# Airq_altium.net
KiCad netlist of a schematic drawn in Altium Designer
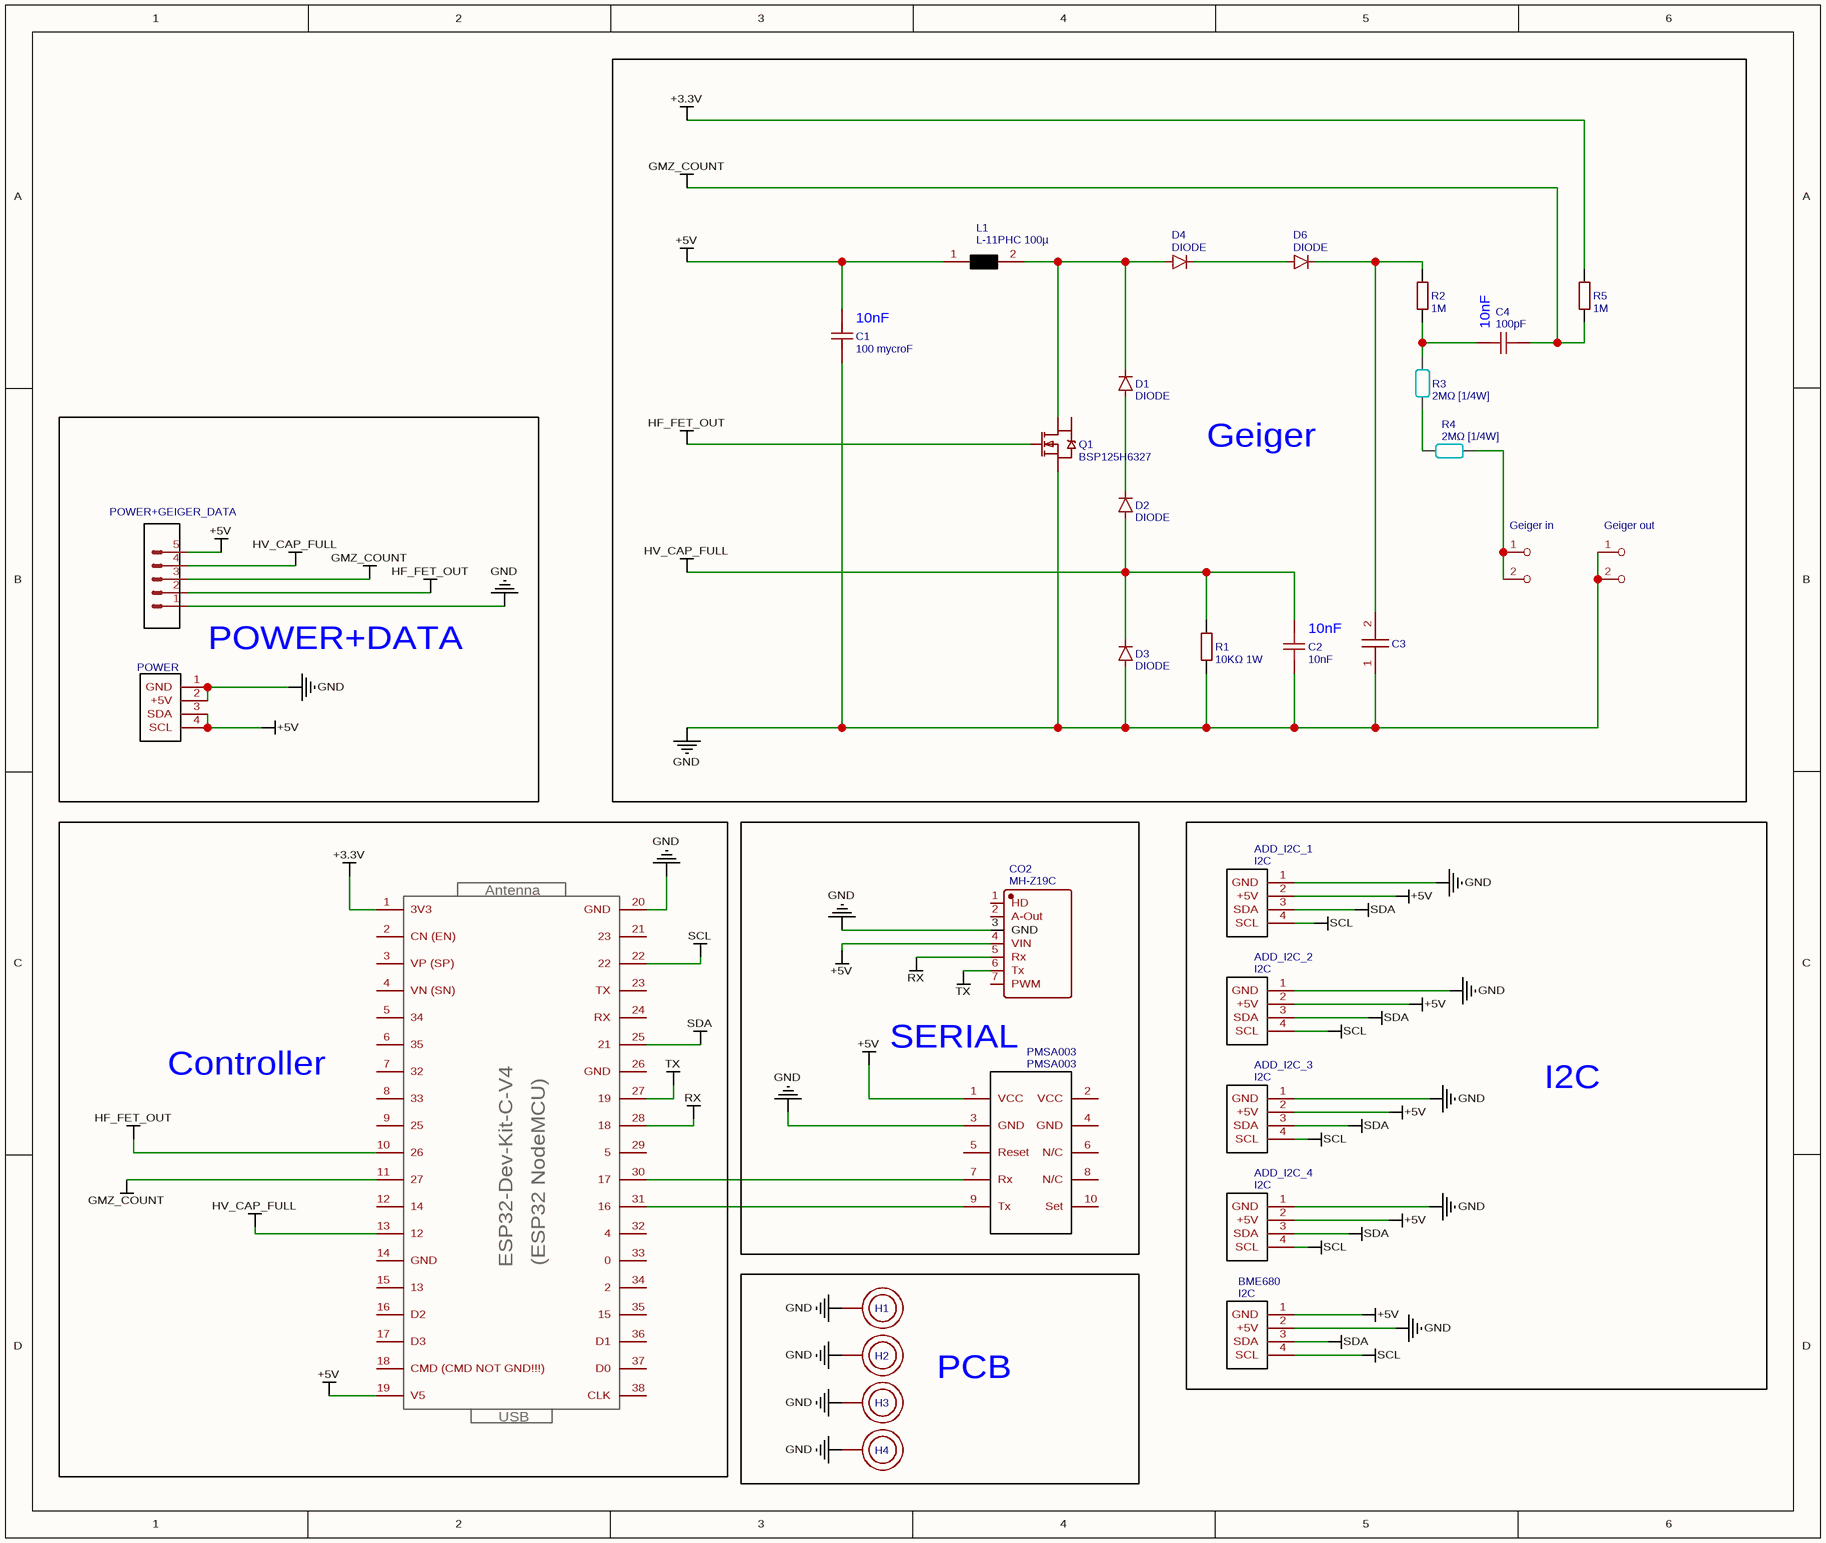
[diagram p0: Airq_altium.schdoc]

(export (version "E")
  (design (tool "Eeschema 10.0.6"))
  (components
    (comp (ref "ADD_I2C_1")
      (value "I2C")
      (fields (field (name "CONTRIBUTOR") "paultwick"))
      (libsource (lib "altium-import") (part "root_0_I2C_"))
    )
    (comp (ref "ADD_I2C_2")
      (value "I2C")
      (fields (field (name "CONTRIBUTOR") "paultwick"))
      (libsource (lib "altium-import") (part "root_0_I2C_"))
    )
    (comp (ref "ADD_I2C_3")
      (value "I2C")
      (fields (field (name "CONTRIBUTOR") "paultwick"))
      (libsource (lib "altium-import") (part "root_0_I2C_"))
    )
    (comp (ref "ADD_I2C_4")
      (value "I2C")
      (fields (field (name "CONTRIBUTOR") "paultwick"))
      (libsource (lib "altium-import") (part "root_0_I2C_"))
    )
    (comp (ref "BME680")
      (value "I2C")
      (fields (field (name "CONTRIBUTOR") "paultwick"))
      (libsource (lib "altium-import") (part "root_0_I2C_"))
    )
    (comp (ref "C1")
      (value "100 mycroF")
      (fields (field (name "CONTRIBUTOR") "Shant Centistoke"))
      (libsource (lib "altium-import") (part "root_0_100 mycroF_"))
    )
    (comp (ref "C2")
      (value "10nF")
      (fields (field (name "CONTRIBUTOR") "Shant Centistoke"))
      (libsource (lib "altium-import") (part "root_0_10nF_"))
    )
    (comp (ref "C3")
      (value "Wima, MKP4, 100nF, 630V")
      (fields (field (name "CONTRIBUTOR") "Hotte"))
      (libsource (lib "altium-import") (part "root_1_Wima, MKP4, 100nF, 630V_"))
    )
    (comp (ref "C4")
      (value "100pF")
      (fields (field (name "CONTRIBUTOR") "Shant Centistoke"))
      (libsource (lib "altium-import") (part "root_1_100pF_"))
    )
    (comp (ref "CO2")
      (value "MH-Z19C")
      (fields
        (field (name "BOM_SUPPLIER PART") "https://github.com/WifWaf/MH-Z19/tree/master/examples/BasicUsage")
        (field (name "CONTRIBUTOR") "Ralf-Michael von Prondzinski")
      )
      (libsource (lib "altium-import") (part "root_0_MH-Z19C_"))
    )
    (comp (ref "D1")
      (value "DIODE")
      (description "Diode")
      (libsource (lib "altium-import") (part "root_1_DIODE_"))
    )
    (comp (ref "D2")
      (value "DIODE")
      (description "Diode")
      (libsource (lib "altium-import") (part "root_1_DIODE_"))
    )
    (comp (ref "D3")
      (value "DIODE")
      (description "Diode")
      (libsource (lib "altium-import") (part "root_1_DIODE_"))
    )
    (comp (ref "D4")
      (value "DIODE")
      (description "Diode")
      (libsource (lib "altium-import") (part "root_0_DIODE_"))
    )
    (comp (ref "D6")
      (value "DIODE")
      (description "Diode")
      (libsource (lib "altium-import") (part "root_0_DIODE_"))
    )
    (comp (ref "H1")
      (value "HoleHole")
      (fields (field (name "CONTRIBUTOR") "Cillié Malan"))
      (libsource (lib "altium-import") (part "root_0_HoleHole_"))
    )
    (comp (ref "H2")
      (value "HoleHole")
      (fields (field (name "CONTRIBUTOR") "Cillié Malan"))
      (libsource (lib "altium-import") (part "root_0_HoleHole_"))
    )
    (comp (ref "H3")
      (value "HoleHole")
      (fields (field (name "CONTRIBUTOR") "Cillié Malan"))
      (libsource (lib "altium-import") (part "root_0_HoleHole_"))
    )
    (comp (ref "H4")
      (value "HoleHole")
      (fields (field (name "CONTRIBUTOR") "Cillié Malan"))
      (libsource (lib "altium-import") (part "root_0_HoleHole_"))
    )
    (comp (ref "JP1")
      (value "Geiger in")
      (fields (field (name "CONTRIBUTOR") "Adafruit"))
      (libsource (lib "altium-import") (part "root_0_Geiger in_"))
    )
    (comp (ref "JP2")
      (value "Geiger out")
      (fields (field (name "CONTRIBUTOR") "Adafruit"))
      (libsource (lib "altium-import") (part "root_0_Geiger out_"))
    )
    (comp (ref "L1")
      (value "L-11PHC 100µ")
      (fields (field (name "CONTRIBUTOR") "Bagger"))
      (libsource (lib "altium-import") (part "root_0_L-11PHC 100µ_"))
    )
    (comp (ref "PMSA003")
      (value "PMSA003")
      (fields (field (name "CONTRIBUTOR") "rajsiman"))
      (libsource (lib "altium-import") (part "root_0_PMSA003_"))
    )
    (comp (ref "POWER")
      (value "Power")
      (fields (field (name "CONTRIBUTOR") "paultwick"))
      (libsource (lib "altium-import") (part "root_0_Power_"))
    )
    (comp (ref "POWER+GEIGER_DATA")
      (value "POWER+GEIGER_DATA")
      (description "5 x 0.1 inch Header")
      (fields (field (name "CONTRIBUTOR") "SparkFun"))
      (libsource (lib "altium-import") (part "root_0_POWER+GEIGER_DATA_"))
    )
    (comp (ref "Q1")
      (value "BSP125H6327")
      (fields (field (name "BOM_SUPPLIER PART") "C123756") (field (name "CONTRIBUTOR") "LCSC"))
      (libsource (lib "altium-import") (part "root_0_BSP125H6327_"))
    )
    (comp (ref "R1")
      (value "10KΩ 1W")
      (fields
        (field (name "BOM_MANUFACTURER PART") "MFR0W4F1004A50")
        (field (name "BOM_SUPPLIER PART") "C58596")
      )
      (libsource (lib "altium-import") (part "root_1_10KΩ 1W_"))
    )
    (comp (ref "R2")
      (value "1M")
      (fields
        (field (name "BOM_MANUFACTURER PART") "MFR0W4F1004A50")
        (field (name "BOM_SUPPLIER PART") "C58596")
      )
      (libsource (lib "altium-import") (part "root_1_1M_"))
    )
    (comp (ref "R3")
      (value "2MΩ [1/4W]")
      (fields
        (field (name "BOM_SUPPLIER PART") "C720290")
        (field (name "CONTRIBUTOR") "Harwave Technologies")
      )
      (libsource (lib "altium-import") (part "root_1_2MΩ [1/4W]_"))
    )
    (comp (ref "R4")
      (value "2MΩ [1/4W]")
      (fields
        (field (name "BOM_SUPPLIER PART") "C720290")
        (field (name "CONTRIBUTOR") "Harwave Technologies")
      )
      (libsource (lib "altium-import") (part "root_0_2MΩ [1/4W]_"))
    )
    (comp (ref "R5")
      (value "1M")
      (fields
        (field (name "BOM_MANUFACTURER PART") "MFR0W4F1004A50")
        (field (name "BOM_SUPPLIER PART") "C58596")
      )
      (libsource (lib "altium-import") (part "root_3_1M_"))
    )
    (comp (ref "U1")
      (value "AZDelivery_ESP32_NodeMCU")
      (fields (field (name "CONTRIBUTOR") "Andreas Riepl"))
      (libsource (lib "altium-import") (part "root_0_AZDelivery_ESP32_NodeMCU_"))
    )
  )
  (nets
    (net (code "1") (name "+3.3V") (class "Default")
      (node (ref "R5") (pin "1") (pinfunction "1_1") (pintype "passive"))
      (node (ref "U1") (pin "1") (pinfunction "3V3_1") (pintype "passive"))
    )
    (net (code "2") (name "+5V") (class "Default")
      (node (ref "ADD_I2C_1") (pin "2") (pinfunction "+5V_2") (pintype "passive"))
      (node (ref "ADD_I2C_2") (pin "2") (pinfunction "+5V_2") (pintype "passive"))
      (node (ref "ADD_I2C_3") (pin "2") (pinfunction "+5V_2") (pintype "passive"))
      (node (ref "ADD_I2C_4") (pin "2") (pinfunction "+5V_2") (pintype "passive"))
      (node (ref "BME680") (pin "1") (pinfunction "GND_1") (pintype "passive"))
      (node (ref "C1") (pin "2") (pinfunction "2_2") (pintype "passive"))
      (node (ref "CO2") (pin "4") (pinfunction "VIN_4") (pintype "passive"))
      (node (ref "L1") (pin "1") (pinfunction "1_1") (pintype "passive"))
      (node (ref "PMSA003") (pin "1") (pinfunction "VCC_1") (pintype "passive"))
      (node (ref "POWER") (pin "3") (pinfunction "SDA_3") (pintype "passive"))
      (node (ref "POWER") (pin "4") (pinfunction "SCL_4") (pintype "passive"))
      (node (ref "POWER+GEIGER_DATA") (pin "5") (pinfunction "1_5") (pintype "passive"))
      (node (ref "U1") (pin "19") (pinfunction "V5_19") (pintype "passive"))
    )
    (net (code "3") (name "GMZ_COUNT") (class "Default")
      (node (ref "C4") (pin "1") (pinfunction "1_1") (pintype "passive"))
      (node (ref "POWER+GEIGER_DATA") (pin "3") (pinfunction "1_3") (pintype "passive"))
      (node (ref "R5") (pin "2") (pinfunction "2_2") (pintype "passive"))
      (node (ref "U1") (pin "11") (pinfunction "27_11") (pintype "passive"))
    )
    (net (code "4") (name "GND") (class "Default")
      (node (ref "ADD_I2C_1") (pin "1") (pinfunction "GND_1") (pintype "passive"))
      (node (ref "ADD_I2C_2") (pin "1") (pinfunction "GND_1") (pintype "passive"))
      (node (ref "ADD_I2C_3") (pin "1") (pinfunction "GND_1") (pintype "passive"))
      (node (ref "ADD_I2C_4") (pin "1") (pinfunction "GND_1") (pintype "passive"))
      (node (ref "BME680") (pin "2") (pinfunction "+5V_2") (pintype "passive"))
      (node (ref "C1") (pin "1") (pinfunction "1_1") (pintype "passive"))
      (node (ref "C2") (pin "1") (pinfunction "1_1") (pintype "passive"))
      (node (ref "C3") (pin "1") (pinfunction "1_1") (pintype "passive"))
      (node (ref "CO2") (pin "3") (pinfunction "GND_3") (pintype "passive"))
      (node (ref "D3") (pin "A") (pinfunction "A_A") (pintype "passive"))
      (node (ref "H1") (pin "1") (pinfunction "1_1") (pintype "passive"))
      (node (ref "H2") (pin "1") (pinfunction "1_1") (pintype "passive"))
      (node (ref "H3") (pin "1") (pinfunction "1_1") (pintype "passive"))
      (node (ref "H4") (pin "1") (pinfunction "1_1") (pintype "passive"))
      (node (ref "JP2") (pin "1") (pinfunction "1_1") (pintype "passive"))
      (node (ref "JP2") (pin "2") (pinfunction "2_2") (pintype "passive"))
      (node (ref "PMSA003") (pin "3") (pinfunction "GND_3") (pintype "passive"))
      (node (ref "POWER") (pin "1") (pinfunction "GND_1") (pintype "passive"))
      (node (ref "POWER") (pin "2") (pinfunction "+5V_2") (pintype "passive"))
      (node (ref "POWER+GEIGER_DATA") (pin "1") (pinfunction "1_1") (pintype "passive"))
      (node (ref "Q1") (pin "3") (pinfunction "S_3") (pintype "passive"))
      (node (ref "R1") (pin "1") (pinfunction "1_1") (pintype "passive"))
      (node (ref "U1") (pin "20") (pinfunction "GND_20") (pintype "passive"))
    )
    (net (code "5") (name "HF_FET_OUT") (class "Default")
      (node (ref "POWER+GEIGER_DATA") (pin "2") (pinfunction "2_2") (pintype "passive"))
      (node (ref "Q1") (pin "1") (pinfunction "G_1") (pintype "passive"))
      (node (ref "U1") (pin "10") (pinfunction "26_10") (pintype "passive"))
    )
    (net (code "6") (name "HV_CAP_FULL") (class "Default")
      (node (ref "C2") (pin "2") (pinfunction "2_2") (pintype "passive"))
      (node (ref "D2") (pin "A") (pinfunction "A_A") (pintype "passive"))
      (node (ref "D3") (pin "C") (pinfunction "C_C") (pintype "passive"))
      (node (ref "POWER+GEIGER_DATA") (pin "4") (pinfunction "2_4") (pintype "passive"))
      (node (ref "R1") (pin "2") (pinfunction "2_2") (pintype "passive"))
      (node (ref "U1") (pin "13") (pinfunction "12_13") (pintype "passive"))
    )
    (net (code "7") (name "Net-(C3-Pad2)") (class "Default")
      (node (ref "C3") (pin "2") (pinfunction "2_2") (pintype "passive"))
      (node (ref "D6") (pin "C") (pinfunction "C_C") (pintype "passive"))
      (node (ref "R2") (pin "2") (pinfunction "2_2") (pintype "passive"))
    )
    (net (code "8") (name "Net-(C4-Pad2)") (class "Default")
      (node (ref "C4") (pin "2") (pinfunction "2_2") (pintype "passive"))
      (node (ref "R2") (pin "1") (pinfunction "1_1") (pintype "passive"))
      (node (ref "R3") (pin "2") (pinfunction "2_2") (pintype "passive"))
    )
    (net (code "9") (name "Net-(D1-PadA)") (class "Default")
      (node (ref "D1") (pin "A") (pinfunction "A_A") (pintype "passive"))
      (node (ref "D2") (pin "C") (pinfunction "C_C") (pintype "passive"))
    )
    (net (code "10") (name "Net-(D1-PadC)") (class "Default")
      (node (ref "D1") (pin "C") (pinfunction "C_C") (pintype "passive"))
      (node (ref "D4") (pin "A") (pinfunction "A_A") (pintype "passive"))
      (node (ref "L1") (pin "2") (pinfunction "2_2") (pintype "passive"))
      (node (ref "Q1") (pin "2") (pinfunction "D_2") (pintype "passive"))
    )
    (net (code "11") (name "Net-(D4-PadC)") (class "Default")
      (node (ref "D4") (pin "C") (pinfunction "C_C") (pintype "passive"))
      (node (ref "D6") (pin "A") (pinfunction "A_A") (pintype "passive"))
    )
    (net (code "12") (name "Net-(JP1-Pad1)") (class "Default")
      (node (ref "JP1") (pin "1") (pinfunction "1_1") (pintype "passive"))
      (node (ref "JP1") (pin "2") (pinfunction "2_2") (pintype "passive"))
      (node (ref "R4") (pin "2") (pinfunction "2_2") (pintype "passive"))
    )
    (net (code "13") (name "Net-(PMSA003-Rx)") (class "Default")
      (node (ref "PMSA003") (pin "7") (pinfunction "Rx_7") (pintype "passive"))
      (node (ref "U1") (pin "30") (pinfunction "17_30") (pintype "passive"))
    )
    (net (code "14") (name "Net-(PMSA003-Tx)") (class "Default")
      (node (ref "PMSA003") (pin "9") (pinfunction "Tx_9") (pintype "passive"))
      (node (ref "U1") (pin "31") (pinfunction "16_31") (pintype "passive"))
    )
    (net (code "15") (name "Net-(R3-Pad1)") (class "Default")
      (node (ref "R3") (pin "1") (pinfunction "1_1") (pintype "passive"))
      (node (ref "R4") (pin "1") (pinfunction "1_1") (pintype "passive"))
    )
    (net (code "16") (name "RX") (class "Default")
      (node (ref "CO2") (pin "5") (pinfunction "Rx_5") (pintype "passive"))
      (node (ref "U1") (pin "28") (pinfunction "18_28") (pintype "passive"))
    )
    (net (code "17") (name "SCL") (class "Default")
      (node (ref "ADD_I2C_1") (pin "4") (pinfunction "SCL_4") (pintype "passive"))
      (node (ref "ADD_I2C_2") (pin "4") (pinfunction "SCL_4") (pintype "passive"))
      (node (ref "ADD_I2C_3") (pin "4") (pinfunction "SCL_4") (pintype "passive"))
      (node (ref "ADD_I2C_4") (pin "4") (pinfunction "SCL_4") (pintype "passive"))
      (node (ref "BME680") (pin "4") (pinfunction "SCL_4") (pintype "passive"))
      (node (ref "U1") (pin "22") (pinfunction "22_22") (pintype "passive"))
    )
    (net (code "18") (name "SDA") (class "Default")
      (node (ref "ADD_I2C_1") (pin "3") (pinfunction "SDA_3") (pintype "passive"))
      (node (ref "ADD_I2C_2") (pin "3") (pinfunction "SDA_3") (pintype "passive"))
      (node (ref "ADD_I2C_3") (pin "3") (pinfunction "SDA_3") (pintype "passive"))
      (node (ref "ADD_I2C_4") (pin "3") (pinfunction "SDA_3") (pintype "passive"))
      (node (ref "BME680") (pin "3") (pinfunction "SDA_3") (pintype "passive"))
      (node (ref "U1") (pin "25") (pinfunction "21_25") (pintype "passive"))
    )
    (net (code "19") (name "TX") (class "Default")
      (node (ref "CO2") (pin "6") (pinfunction "Tx_6") (pintype "passive"))
      (node (ref "U1") (pin "27") (pinfunction "19_27") (pintype "passive"))
    )
    (net (code "20") (name "unconnected-(CO2-A-Out-Pad2)") (class "Default")
      (node (ref "CO2") (pin "2") (pinfunction "A-Out_2") (pintype "passive"))
    )
    (net (code "21") (name "unconnected-(CO2-HD-Pad1)") (class "Default")
      (node (ref "CO2") (pin "1") (pinfunction "HD_1") (pintype "passive"))
    )
    (net (code "22") (name "unconnected-(CO2-PWM-Pad7)") (class "Default")
      (node (ref "CO2") (pin "7") (pinfunction "PWM_7") (pintype "passive"))
    )
    (net (code "23") (name "unconnected-(PMSA003-GND-Pad4)") (class "Default")
      (node (ref "PMSA003") (pin "4") (pinfunction "GND_4") (pintype "passive"))
    )
    (net (code "24") (name "unconnected-(PMSA003-N{slash}C-Pad6)") (class "Default")
      (node (ref "PMSA003") (pin "6") (pinfunction "N/C_6") (pintype "passive"))
    )
    (net (code "25") (name "unconnected-(PMSA003-N{slash}C-Pad8)") (class "Default")
      (node (ref "PMSA003") (pin "8") (pinfunction "N/C_8") (pintype "passive"))
    )
    (net (code "26") (name "unconnected-(PMSA003-Reset-Pad5)") (class "Default")
      (node (ref "PMSA003") (pin "5") (pinfunction "Reset_5") (pintype "passive"))
    )
    (net (code "27") (name "unconnected-(PMSA003-Set-Pad10)") (class "Default")
      (node (ref "PMSA003") (pin "10") (pinfunction "Set_10") (pintype "passive"))
    )
    (net (code "28") (name "unconnected-(PMSA003-VCC-Pad2)") (class "Default")
      (node (ref "PMSA003") (pin "2") (pinfunction "VCC_2") (pintype "passive"))
    )
    (net (code "29") (name "unconnected-(Q1-D-Pad4)") (class "Default")
      (node (ref "Q1") (pin "4") (pinfunction "D_4") (pintype "passive"))
    )
    (net (code "30") (name "unconnected-(U1-0-Pad33)") (class "Default")
      (node (ref "U1") (pin "33") (pinfunction "0_33") (pintype "passive"))
    )
    (net (code "31") (name "unconnected-(U1-2-Pad34)") (class "Default")
      (node (ref "U1") (pin "34") (pinfunction "2_34") (pintype "passive"))
    )
    (net (code "32") (name "unconnected-(U1-4-Pad32)") (class "Default")
      (node (ref "U1") (pin "32") (pinfunction "4_32") (pintype "passive"))
    )
    (net (code "33") (name "unconnected-(U1-5-Pad29)") (class "Default")
      (node (ref "U1") (pin "29") (pinfunction "5_29") (pintype "passive"))
    )
    (net (code "34") (name "unconnected-(U1-13-Pad15)") (class "Default")
      (node (ref "U1") (pin "15") (pinfunction "13_15") (pintype "passive"))
    )
    (net (code "35") (name "unconnected-(U1-14-Pad12)") (class "Default")
      (node (ref "U1") (pin "12") (pinfunction "14_12") (pintype "passive"))
    )
    (net (code "36") (name "unconnected-(U1-15-Pad35)") (class "Default")
      (node (ref "U1") (pin "35") (pinfunction "15_35") (pintype "passive"))
    )
    (net (code "37") (name "unconnected-(U1-23-Pad21)") (class "Default")
      (node (ref "U1") (pin "21") (pinfunction "23_21") (pintype "passive"))
    )
    (net (code "38") (name "unconnected-(U1-25-Pad9)") (class "Default")
      (node (ref "U1") (pin "9") (pinfunction "25_9") (pintype "passive"))
    )
    (net (code "39") (name "unconnected-(U1-32-Pad7)") (class "Default")
      (node (ref "U1") (pin "7") (pinfunction "32_7") (pintype "passive"))
    )
    (net (code "40") (name "unconnected-(U1-33-Pad8)") (class "Default")
      (node (ref "U1") (pin "8") (pinfunction "33_8") (pintype "passive"))
    )
    (net (code "41") (name "unconnected-(U1-34-Pad5)") (class "Default")
      (node (ref "U1") (pin "5") (pinfunction "34_5") (pintype "passive"))
    )
    (net (code "42") (name "unconnected-(U1-35-Pad6)") (class "Default")
      (node (ref "U1") (pin "6") (pinfunction "35_6") (pintype "passive"))
    )
    (net (code "43") (name "unconnected-(U1-CLK-Pad38)") (class "Default")
      (node (ref "U1") (pin "38") (pinfunction "CLK_38") (pintype "passive"))
    )
    (net (code "44") (name "unconnected-(U1-CMD_(CMD_NOT_GND!!!)-Pad18)") (class "Default")
      (node (ref "U1") (pin "18") (pinfunction "CMD_(CMD_NOT_GND!!!)_18") (pintype "passive"))
    )
    (net (code "45") (name "unconnected-(U1-CN_(EN)-Pad2)") (class "Default")
      (node (ref "U1") (pin "2") (pinfunction "CN_(EN)_2") (pintype "passive"))
    )
    (net (code "46") (name "unconnected-(U1-D0-Pad37)") (class "Default")
      (node (ref "U1") (pin "37") (pinfunction "D0_37") (pintype "passive"))
    )
    (net (code "47") (name "unconnected-(U1-D1-Pad36)") (class "Default")
      (node (ref "U1") (pin "36") (pinfunction "D1_36") (pintype "passive"))
    )
    (net (code "48") (name "unconnected-(U1-D2-Pad16)") (class "Default")
      (node (ref "U1") (pin "16") (pinfunction "D2_16") (pintype "passive"))
    )
    (net (code "49") (name "unconnected-(U1-D3-Pad17)") (class "Default")
      (node (ref "U1") (pin "17") (pinfunction "D3_17") (pintype "passive"))
    )
    (net (code "50") (name "unconnected-(U1-GND-Pad14)") (class "Default")
      (node (ref "U1") (pin "14") (pinfunction "GND_14") (pintype "passive"))
    )
    (net (code "51") (name "unconnected-(U1-GND-Pad26)") (class "Default")
      (node (ref "U1") (pin "26") (pinfunction "GND_26") (pintype "passive"))
    )
    (net (code "52") (name "unconnected-(U1-RX-Pad24)") (class "Default")
      (node (ref "U1") (pin "24") (pinfunction "RX_24") (pintype "passive"))
    )
    (net (code "53") (name "unconnected-(U1-TX-Pad23)") (class "Default")
      (node (ref "U1") (pin "23") (pinfunction "TX_23") (pintype "passive"))
    )
    (net (code "54") (name "unconnected-(U1-VN_(SN)-Pad4)") (class "Default")
      (node (ref "U1") (pin "4") (pinfunction "VN_(SN)_4") (pintype "passive"))
    )
    (net (code "55") (name "unconnected-(U1-VP_(SP)-Pad3)") (class "Default")
      (node (ref "U1") (pin "3") (pinfunction "VP_(SP)_3") (pintype "passive"))
    )
  )
)
